# STM32F103-V1_0.net
KiCad netlist of a schematic drawn in Altium Designer
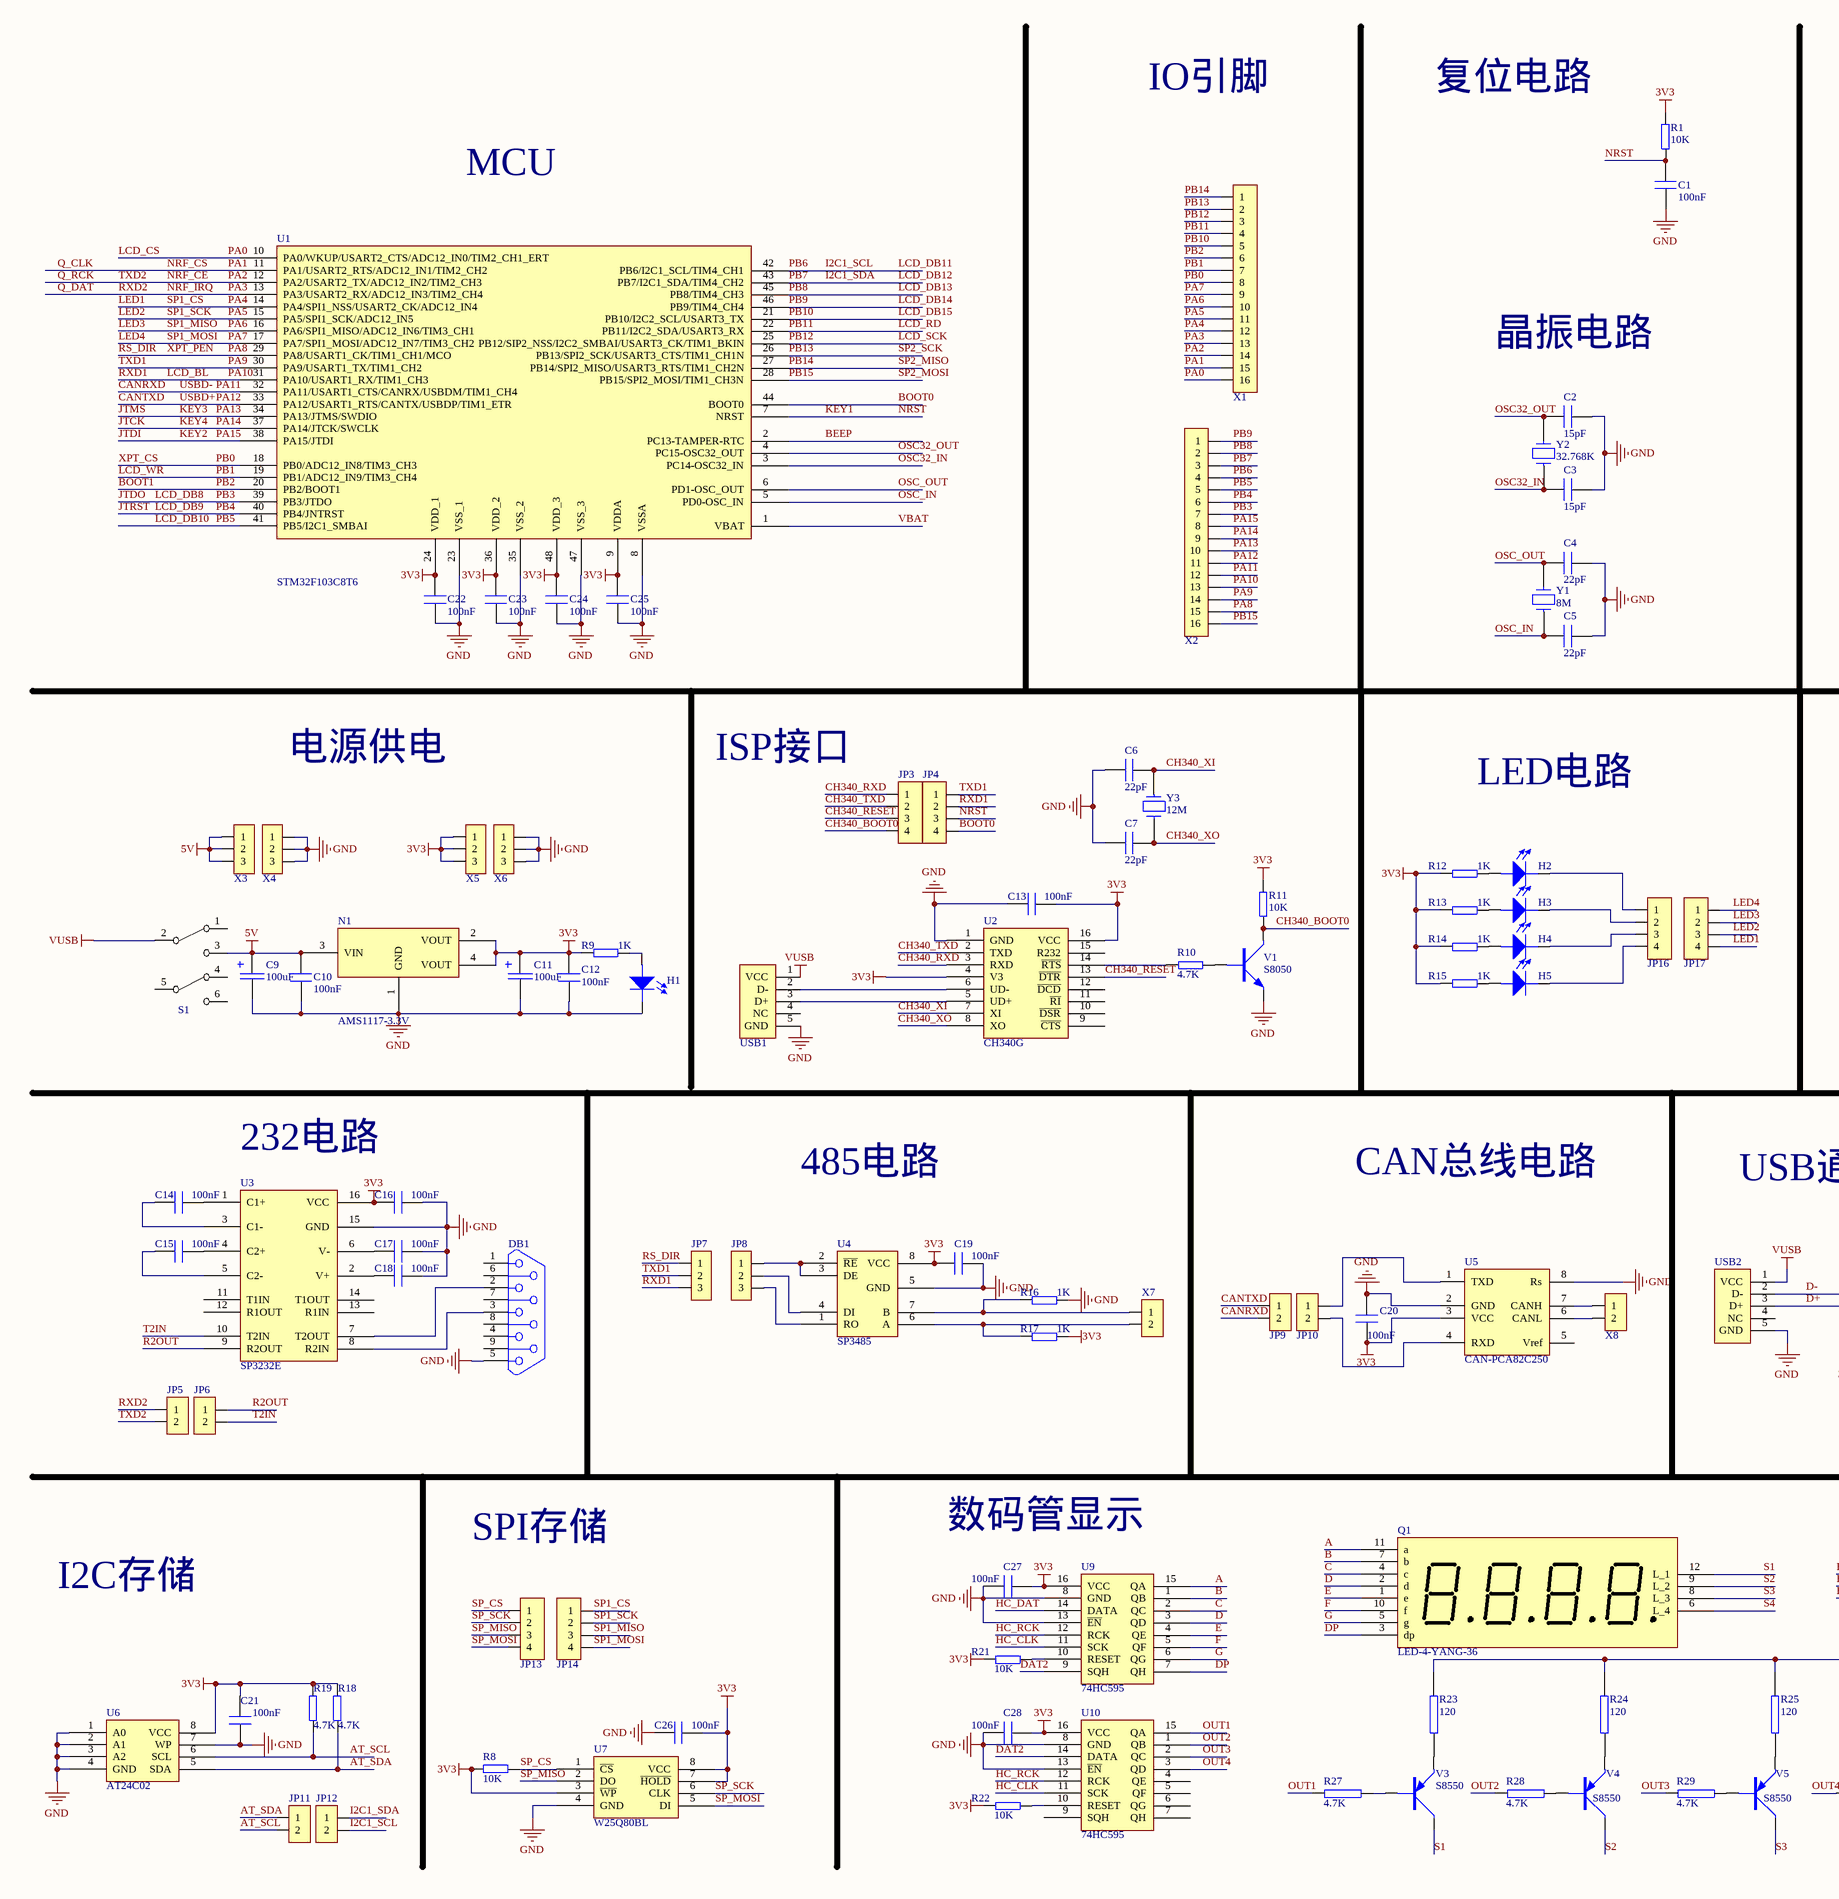
[diagram p0: STM32F103-V1.0.SchDoc, left]
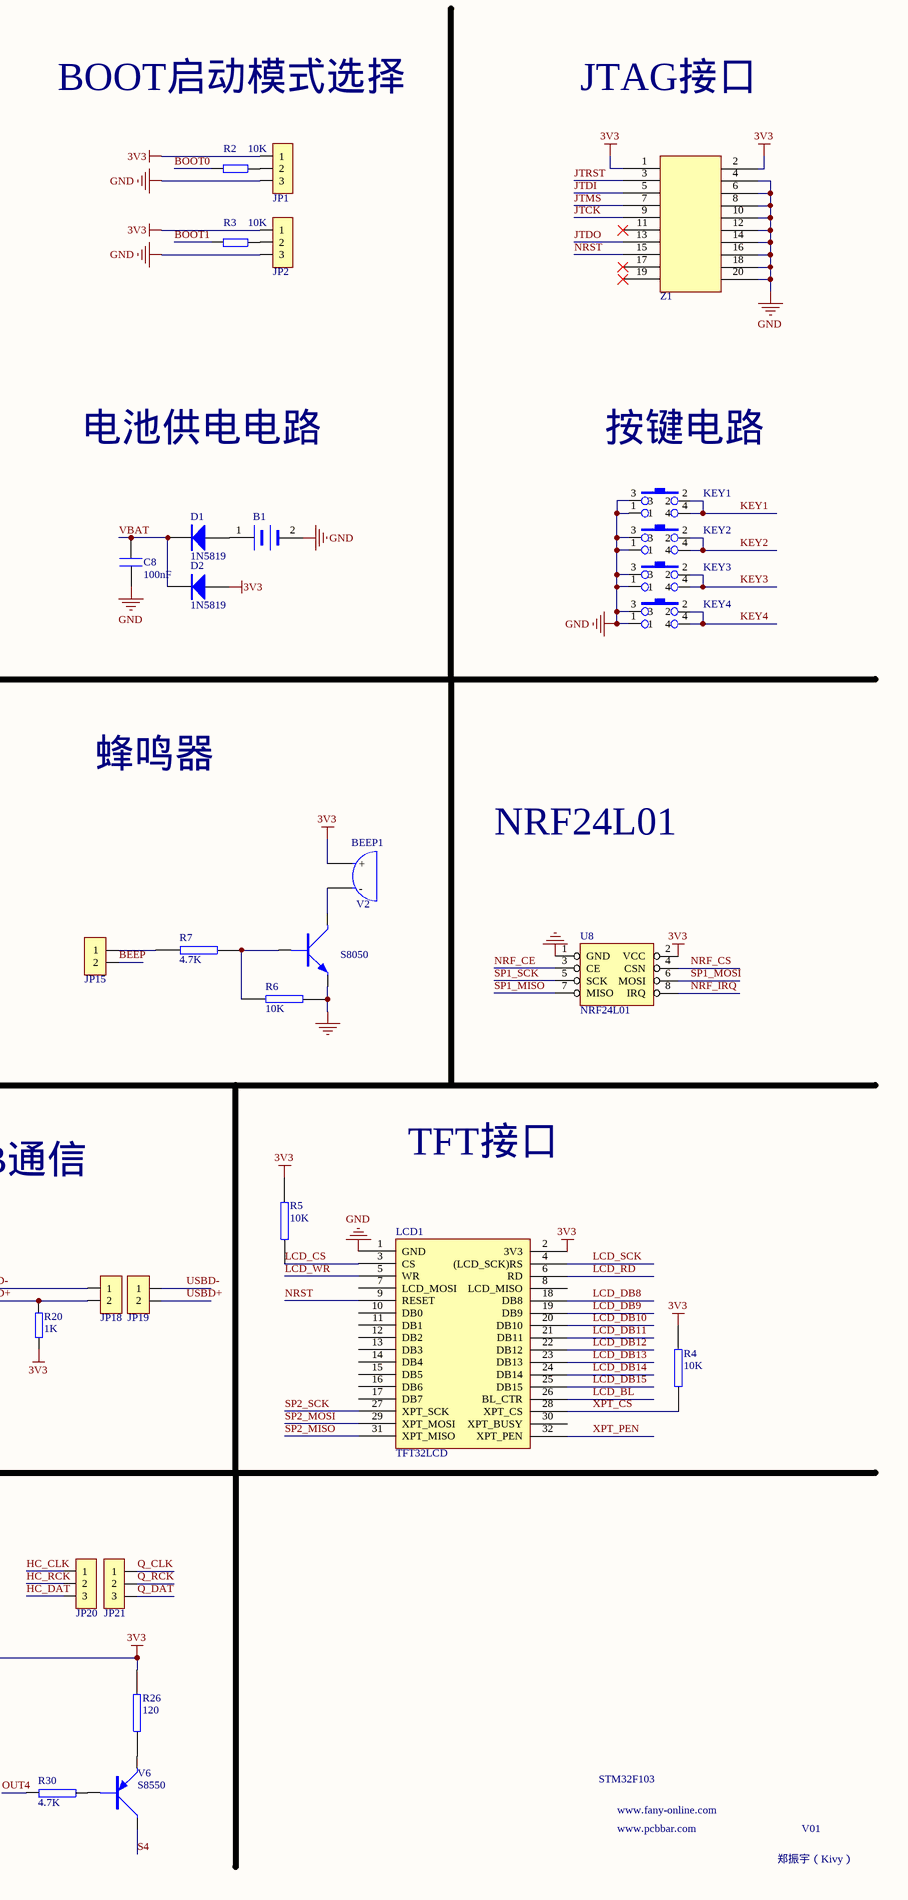
[diagram p1: STM32F103-V1.0.SchDoc, right]

(export (version "E")
  (design (tool "Eeschema 10.0.6"))
  (components
    (comp (ref "B1") (value "BATTERY") (footprint "CR1220") (libsource (lib "Liuzhx") (part "BATTERY")))
    (comp (ref "BEEP1") (value "BEEP") (footprint "SOT12-7.6") (libsource (lib "RationSTM32") (part "BEEP")))
    (comp (ref "C1")
      (value "100nF")
      (footprint "C0805")
      (description "Capacitor")
      (libsource (lib "Liuzhx") (part "普通贴片电容"))
    )
    (comp (ref "C2")
      (value "15pF")
      (footprint "C0805")
      (description "Capacitor")
      (libsource (lib "Liuzhx") (part "普通贴片电容"))
    )
    (comp (ref "C3")
      (value "15pF")
      (footprint "C0805")
      (description "Capacitor")
      (libsource (lib "Liuzhx") (part "普通贴片电容"))
    )
    (comp (ref "C4")
      (value "22pF")
      (footprint "C0805")
      (description "Capacitor")
      (libsource (lib "Liuzhx") (part "普通贴片电容"))
    )
    (comp (ref "C5")
      (value "22pF")
      (footprint "C0805")
      (description "Capacitor")
      (libsource (lib "Liuzhx") (part "普通贴片电容"))
    )
    (comp (ref "C6")
      (value "22pF")
      (footprint "C0805")
      (description "Capacitor")
      (libsource (lib "Liuzhx") (part "普通贴片电容"))
    )
    (comp (ref "C7")
      (value "22pF")
      (footprint "C0805")
      (description "Capacitor")
      (libsource (lib "Liuzhx") (part "普通贴片电容"))
    )
    (comp (ref "C8")
      (value "100nF")
      (footprint "C0805")
      (description "Capacitor")
      (libsource (lib "Liuzhx") (part "普通贴片电容"))
    )
    (comp (ref "C9") (value "100uF") (footprint "CAP5*5_4") (libsource (lib "Liuzhx") (part "极性电容器")))
    (comp (ref "C10")
      (value "100nF")
      (footprint "C0805")
      (description "Capacitor")
      (libsource (lib "Liuzhx") (part "普通贴片电容"))
    )
    (comp (ref "C11") (value "100uF") (footprint "CAP5*5_4") (libsource (lib "Liuzhx") (part "极性电容器")))
    (comp (ref "C12")
      (value "100nF")
      (footprint "C0805")
      (description "Capacitor")
      (libsource (lib "Liuzhx") (part "普通贴片电容"))
    )
    (comp (ref "C13")
      (value "100nF")
      (footprint "C0805")
      (description "Capacitor")
      (libsource (lib "Liuzhx") (part "普通贴片电容"))
    )
    (comp (ref "C14")
      (value "100nF")
      (footprint "C0805")
      (description "Capacitor")
      (libsource (lib "Liuzhx") (part "普通贴片电容"))
    )
    (comp (ref "C15")
      (value "100nF")
      (footprint "C0805")
      (description "Capacitor")
      (libsource (lib "Liuzhx") (part "普通贴片电容"))
    )
    (comp (ref "C16")
      (value "100nF")
      (footprint "C0805")
      (description "Capacitor")
      (libsource (lib "Liuzhx") (part "普通贴片电容"))
    )
    (comp (ref "C17")
      (value "100nF")
      (footprint "C0805")
      (description "Capacitor")
      (libsource (lib "Liuzhx") (part "普通贴片电容"))
    )
    (comp (ref "C18")
      (value "100nF")
      (footprint "C0805")
      (description "Capacitor")
      (libsource (lib "Liuzhx") (part "普通贴片电容"))
    )
    (comp (ref "C19")
      (value "100nF")
      (footprint "C0805")
      (description "Capacitor")
      (libsource (lib "Liuzhx") (part "普通贴片电容"))
    )
    (comp (ref "C20")
      (value "100nF")
      (footprint "C0805")
      (description "Capacitor")
      (libsource (lib "GKSSCH") (part "普通贴片电容"))
    )
    (comp (ref "C21")
      (value "100nF")
      (footprint "C0805")
      (description "Capacitor")
      (libsource (lib "Liuzhx") (part "普通贴片电容"))
    )
    (comp (ref "C22")
      (value "100nF")
      (footprint "C0805")
      (description "Capacitor")
      (libsource (lib "Liuzhx") (part "普通贴片电容"))
    )
    (comp (ref "C23")
      (value "100nF")
      (footprint "C0805")
      (description "Capacitor")
      (libsource (lib "Liuzhx") (part "普通贴片电容"))
    )
    (comp (ref "C24")
      (value "100nF")
      (footprint "C0805")
      (description "Capacitor")
      (libsource (lib "Liuzhx") (part "普通贴片电容"))
    )
    (comp (ref "C25")
      (value "100nF")
      (footprint "C0805")
      (description "Capacitor")
      (libsource (lib "Liuzhx") (part "普通贴片电容"))
    )
    (comp (ref "C26")
      (value "100nF")
      (footprint "C0805")
      (description "Capacitor")
      (libsource (lib "Liuzhx") (part "普通贴片电容"))
    )
    (comp (ref "C27")
      (value "100nF")
      (footprint "C0805")
      (description "Capacitor")
      (libsource (lib "Liuzhx") (part "普通贴片电容"))
    )
    (comp (ref "C28")
      (value "100nF")
      (footprint "C0805")
      (description "Capacitor")
      (libsource (lib "Liuzhx") (part "普通贴片电容"))
    )
    (comp (ref "D1")
      (value "1N5819")
      (footprint "1N4148-T")
      (description "Diode 1N series")
      (libsource (lib "Liuzhx") (part "贴片二极管"))
    )
    (comp (ref "D2")
      (value "1N5819")
      (footprint "1N4148-T")
      (description "Diode 1N series")
      (libsource (lib "Liuzhx") (part "贴片二极管"))
    )
    (comp (ref "DB1")
      (value "DB9M")
      (footprint "DB9-M")
      (description "母头")
      (libsource (lib "Liuzhx") (part "DB9M"))
    )
    (comp (ref "H1") (value "发光二极管") (footprint "LED1206") (libsource (lib "Liuzhx") (part "发光二极管")))
    (comp (ref "H2") (value "发光二极管") (footprint "LED1206") (libsource (lib "Liuzhx") (part "发光二极管")))
    (comp (ref "H3") (value "发光二极管") (footprint "LED1206") (libsource (lib "Liuzhx") (part "发光二极管")))
    (comp (ref "H4") (value "发光二极管") (footprint "LED1206") (libsource (lib "Liuzhx") (part "发光二极管")))
    (comp (ref "H5") (value "发光二极管") (footprint "LED1206") (libsource (lib "Liuzhx") (part "发光二极管")))
    (comp (ref "JP1")
      (value "JX3")
      (footprint "SIP3")
      (description "Connector")
      (libsource (lib "Liuzhx") (part "JX3"))
    )
    (comp (ref "JP2")
      (value "JX3")
      (footprint "SIP3")
      (description "Connector")
      (libsource (lib "Liuzhx") (part "JX3"))
    )
    (comp (ref "JP3")
      (value "JX4")
      (footprint "SIP4")
      (description "Connector")
      (libsource (lib "Liuzhx") (part "JX4"))
    )
    (comp (ref "JP4")
      (value "JX4")
      (footprint "SIP4")
      (description "Connector")
      (libsource (lib "") (part "JX4_1"))
    )
    (comp (ref "JP5")
      (value "JX2")
      (footprint "SIP2")
      (description "Connector")
      (libsource (lib "") (part "JX2_1"))
    )
    (comp (ref "JP6")
      (value "JX2")
      (footprint "SIP2")
      (description "Connector")
      (libsource (lib "Liuzhx") (part "JX2"))
    )
    (comp (ref "JP7")
      (value "JX3")
      (footprint "SIP3")
      (description "Connector")
      (libsource (lib "Liuzhx") (part "JX3"))
    )
    (comp (ref "JP8")
      (value "JX3")
      (footprint "SIP3")
      (description "Connector")
      (libsource (lib "") (part "JX3_1"))
    )
    (comp (ref "JP9")
      (value "JX2")
      (footprint "SIP2")
      (description "Connector")
      (libsource (lib "GKSSCH") (part "JX2"))
    )
    (comp (ref "JP10")
      (value "JX2")
      (footprint "SIP2")
      (description "Connector")
      (libsource (lib "") (part "JX2_1"))
    )
    (comp (ref "JP11")
      (value "JX2")
      (footprint "SIP2")
      (description "Connector")
      (libsource (lib "") (part "JX2_1"))
    )
    (comp (ref "JP12")
      (value "JX2")
      (footprint "SIP2")
      (description "Connector")
      (libsource (lib "Liuzhx") (part "JX2"))
    )
    (comp (ref "JP13")
      (value "JX4")
      (footprint "SIP4")
      (description "Connector")
      (libsource (lib "Liuzhx") (part "JX4"))
    )
    (comp (ref "JP14")
      (value "JX4")
      (footprint "SIP4")
      (description "Connector")
      (libsource (lib "") (part "JX4_1"))
    )
    (comp (ref "JP15")
      (value "JX2")
      (footprint "SIP2")
      (description "Connector")
      (libsource (lib "Liuzhx") (part "JX2"))
    )
    (comp (ref "JP16")
      (value "JX4")
      (footprint "SIP4")
      (description "Connector")
      (libsource (lib "Liuzhx") (part "JX4"))
    )
    (comp (ref "JP17")
      (value "JX4")
      (footprint "SIP4")
      (description "Connector")
      (libsource (lib "") (part "JX4_1"))
    )
    (comp (ref "JP18")
      (value "JX2")
      (footprint "SIP2")
      (description "Connector")
      (libsource (lib "") (part "JX2_1"))
    )
    (comp (ref "JP19")
      (value "JX2")
      (footprint "SIP2")
      (description "Connector")
      (libsource (lib "Liuzhx") (part "JX2"))
    )
    (comp (ref "JP20")
      (value "JX3")
      (footprint "SIP3")
      (description "Connector")
      (libsource (lib "Liuzhx") (part "JX3"))
    )
    (comp (ref "JP21")
      (value "JX3")
      (footprint "SIP3")
      (description "Connector")
      (libsource (lib "") (part "JX3_1"))
    )
    (comp (ref "KEY1") (value "SW-66B7") (footprint "SW-66") (libsource (lib "Liuzhx") (part "SW-66B7")))
    (comp (ref "KEY2") (value "SW-66B7") (footprint "SW-66") (libsource (lib "Liuzhx") (part "SW-66B7")))
    (comp (ref "KEY3") (value "SW-66B7") (footprint "SW-66") (libsource (lib "Liuzhx") (part "SW-66B7")))
    (comp (ref "KEY4") (value "SW-66B7") (footprint "SW-66") (libsource (lib "Liuzhx") (part "SW-66B7")))
    (comp (ref "LCD1") (value "TFT32LCD") (footprint "HEAD16×2") (libsource (lib "Liuzhx") (part "TFT32LCD")))
    (comp (ref "N1")
      (value "AMS1117-3.3V")
      (footprint "SOT223")
      (libsource (lib "Liuzhx") (part "AMS1117-3.3V"))
    )
    (comp (ref "Q1")
      (value "LED-4-YANG-36")
      (footprint "LED0.36-4")
      (libsource (lib "Liuzhx") (part "LED-4-YANG-36"))
    )
    (comp (ref "R1") (value "10K") (footprint "R0805") (libsource (lib "Liuzhx") (part "普通贴片电阻")))
    (comp (ref "R2") (value "10K") (footprint "R0805") (libsource (lib "Liuzhx") (part "普通贴片电阻")))
    (comp (ref "R3") (value "10K") (footprint "R0805") (libsource (lib "Liuzhx") (part "普通贴片电阻")))
    (comp (ref "R4") (value "10K") (footprint "R0805") (libsource (lib "RationSTM32") (part "RES")))
    (comp (ref "R5") (value "10K") (footprint "R0805") (libsource (lib "RationSTM32") (part "RES")))
    (comp (ref "R6") (value "10K") (footprint "R0805") (libsource (lib "RationSTM32") (part "RES")))
    (comp (ref "R7") (value "4.7K") (footprint "R0805") (libsource (lib "RationSTM32") (part "RES")))
    (comp (ref "R8") (value "10K") (footprint "R0805") (libsource (lib "Liuzhx") (part "普通贴片电阻")))
    (comp (ref "R9") (value "1K") (footprint "R0805") (libsource (lib "Liuzhx") (part "普通贴片电阻")))
    (comp (ref "R10") (value "4.7K") (footprint "R0805") (libsource (lib "Liuzhx") (part "普通贴片电阻")))
    (comp (ref "R11") (value "10K") (footprint "R0805") (libsource (lib "Liuzhx") (part "普通贴片电阻")))
    (comp (ref "R12") (value "1K") (footprint "R0805") (libsource (lib "Liuzhx") (part "普通贴片电阻")))
    (comp (ref "R13") (value "1K") (footprint "R0805") (libsource (lib "Liuzhx") (part "普通贴片电阻")))
    (comp (ref "R14") (value "1K") (footprint "R0805") (libsource (lib "Liuzhx") (part "普通贴片电阻")))
    (comp (ref "R15") (value "1K") (footprint "R0805") (libsource (lib "Liuzhx") (part "普通贴片电阻")))
    (comp (ref "R16") (value "1K") (footprint "R0805") (libsource (lib "Liuzhx") (part "普通贴片电阻")))
    (comp (ref "R17") (value "1K") (footprint "R0805") (libsource (lib "Liuzhx") (part "普通贴片电阻")))
    (comp (ref "R18") (value "4.7K") (footprint "R0805") (libsource (lib "Liuzhx") (part "普通贴片电阻")))
    (comp (ref "R19") (value "4.7K") (footprint "R0805") (libsource (lib "Liuzhx") (part "普通贴片电阻")))
    (comp (ref "R20") (value "1K") (footprint "R0805") (libsource (lib "Liuzhx") (part "普通贴片电阻")))
    (comp (ref "R21") (value "10K") (footprint "R0805") (libsource (lib "Liuzhx") (part "普通贴片电阻")))
    (comp (ref "R22") (value "10K") (footprint "R0805") (libsource (lib "Liuzhx") (part "普通贴片电阻")))
    (comp (ref "R23") (value "120") (footprint "R0805") (libsource (lib "STM32F103-V1.0") (part "RES")))
    (comp (ref "R24") (value "120") (footprint "R0805") (libsource (lib "STM32F103-V1.0") (part "RES")))
    (comp (ref "R25") (value "120") (footprint "R0805") (libsource (lib "STM32F103-V1.0") (part "RES")))
    (comp (ref "R26") (value "120") (footprint "R0805") (libsource (lib "STM32F103-V1.0") (part "RES")))
    (comp (ref "R27") (value "4.7K") (footprint "R0805") (libsource (lib "STM32F103-V1.0") (part "RES2")))
    (comp (ref "R28") (value "4.7K") (footprint "R0805") (libsource (lib "STM32F103-V1.0") (part "RES2")))
    (comp (ref "R29") (value "4.7K") (footprint "R0805") (libsource (lib "STM32F103-V1.0") (part "RES2")))
    (comp (ref "R30") (value "4.7K") (footprint "R0805") (libsource (lib "STM32F103-V1.0") (part "RES2")))
    (comp (ref "S1") (value "SWITCH-6") (footprint "SW-AJ") (libsource (lib "Liuzhx") (part "SWITCH-6")))
    (comp (ref "U1")
      (value "STM32F103C8T6")
      (footprint "LQFP48")
      (libsource (lib "STM32F103-V1.0") (part "STM32F103C8T6"))
    )
    (comp (ref "U2") (value "CH340G") (footprint "SOIC16") (libsource (lib "Liuzhx") (part "CH340G")))
    (comp (ref "U3")
      (value "SP3232E")
      (footprint "SOIC16")
      (description "SP3232EEN-L/TR;SOIC-39MM")
      (libsource (lib "Liuzhx") (part "SP3232E"))
    )
    (comp (ref "U4") (value "SP3485") (footprint "SO-8") (libsource (lib "Liuzhx") (part "MAX3082")))
    (comp (ref "U5")
      (value "CAN-PCA82C250")
      (footprint "SO-8")
      (libsource (lib "GKSSCH") (part "CAN-PCA82C250"))
    )
    (comp (ref "U6") (value "AT24C02") (footprint "SO-8") (libsource (lib "Liuzhx") (part "AT24C02")))
    (comp (ref "U7") (value "W25Q80BL") (footprint "W25Q-SO8") (libsource (lib "Liuzhx") (part "W25Q80BL")))
    (comp (ref "U8") (value "NRF24L01") (footprint "NRF24L01") (libsource (lib "Liuzhx") (part "NRF24L01")))
    (comp (ref "U9")
      (value "74HC595")
      (footprint "SO-16")
      (description "串入并出移位寄存器")
      (libsource (lib "Liuzhx") (part "74HC595"))
    )
    (comp (ref "U10")
      (value "74HC595")
      (footprint "SO-16")
      (description "串入并出移位寄存器")
      (libsource (lib "Liuzhx") (part "74HC595"))
    )
    (comp (ref "USB1")
      (value "MicroUSB")
      (footprint "MicroUSB1")
      (description "母头")
      (libsource (lib "Liuzhx") (part "MicroUSB"))
    )
    (comp (ref "USB2")
      (value "MicroUSB")
      (footprint "MicroUSB1")
      (description "母头")
      (libsource (lib "Liuzhx") (part "MicroUSB"))
    )
    (comp (ref "V1")
      (value "S8050")
      (footprint "SOT23-C1")
      (description "V")
      (libsource (lib "Liuzhx") (part "NPN三极管"))
    )
    (comp (ref "V2")
      (value "S8050")
      (footprint "SOT23-C1")
      (description "V")
      (libsource (lib "Liuzhx") (part "NPN三极管"))
    )
    (comp (ref "V3")
      (value "S8550")
      (footprint "SOT23-C1")
      (description "V")
      (libsource (lib "*") (part "PNP三极管"))
    )
    (comp (ref "V4")
      (value "S8550")
      (footprint "SOT23-C1")
      (description "V")
      (libsource (lib "*") (part "PNP三极管"))
    )
    (comp (ref "V5")
      (value "S8550")
      (footprint "SOT23-C1")
      (description "V")
      (libsource (lib "*") (part "PNP三极管"))
    )
    (comp (ref "V6")
      (value "S8550")
      (footprint "SOT23-C1")
      (description "V")
      (libsource (lib "*") (part "PNP三极管"))
    )
    (comp (ref "X1") (value "JX16") (footprint "SIP16") (libsource (lib "") (part "JX16_1")))
    (comp (ref "X2") (value "JX16") (footprint "SIP16") (libsource (lib "Liuzhx") (part "JX16")))
    (comp (ref "X3")
      (value "JX3")
      (footprint "SIP3")
      (description "Connector")
      (libsource (lib "Liuzhx") (part "JX3"))
    )
    (comp (ref "X4")
      (value "JX3")
      (footprint "SIP3")
      (description "Connector")
      (libsource (lib "") (part "JX3_1"))
    )
    (comp (ref "X5")
      (value "JX3")
      (footprint "SIP3")
      (description "Connector")
      (libsource (lib "Liuzhx") (part "JX3"))
    )
    (comp (ref "X6")
      (value "JX3")
      (footprint "SIP3")
      (description "Connector")
      (libsource (lib "") (part "JX3_1"))
    )
    (comp (ref "X7")
      (value "JX2")
      (footprint "WJ128-5.0-2P")
      (description "Connector")
      (libsource (lib "") (part "JX2_1"))
    )
    (comp (ref "X8")
      (value "JX2")
      (footprint "WJ128-5.0-2P")
      (description "Connector")
      (libsource (lib "GKSSCH") (part "JX2"))
    )
    (comp (ref "Y1")
      (value "8M")
      (footprint "JZ-AX")
      (description "Crystal")
      (libsource (lib "Liuzhx") (part "CRYSTAL"))
    )
    (comp (ref "Y2")
      (value "32.768K")
      (footprint "FC135")
      (description "Crystal")
      (libsource (lib "Liuzhx") (part "CRYSTAL"))
    )
    (comp (ref "Y3")
      (value "12M")
      (footprint "JZ-AX")
      (description "Crystal")
      (libsource (lib "Liuzhx") (part "CRYSTAL"))
    )
    (comp (ref "Z1") (value "HEADER 10X2") (footprint "JTAG") (libsource (lib "STM32") (part "HEADER 10X2")))
  )
  (nets
    (net (code "1") (name "/A") (class "Default")
      (node (ref "Q1") (pin "11") (pinfunction "a_11") (pintype "passive"))
      (node (ref "U9") (pin "15") (pinfunction "QA_15") (pintype "passive"))
    )
    (net (code "2") (name "/AT_SCL") (class "Default")
      (node (ref "JP11") (pin "2") (pinfunction "2_2") (pintype "passive"))
      (node (ref "R19") (pin "1") (pinfunction "1_1") (pintype "passive"))
      (node (ref "U6") (pin "6") (pinfunction "SCL_6") (pintype "passive"))
    )
    (net (code "3") (name "/AT_SDA") (class "Default")
      (node (ref "JP11") (pin "1") (pinfunction "1_1") (pintype "passive"))
      (node (ref "R18") (pin "1") (pinfunction "1_1") (pintype "passive"))
      (node (ref "U6") (pin "5") (pinfunction "SDA_5") (pintype "passive"))
    )
    (net (code "4") (name "/B") (class "Default")
      (node (ref "Q1") (pin "7") (pinfunction "b_7") (pintype "passive"))
      (node (ref "U9") (pin "1") (pinfunction "QB_1") (pintype "passive"))
    )
    (net (code "5") (name "/BEEP") (class "Default")
      (node (ref "JP15") (pin "2") (pinfunction "2_2") (pintype "passive"))
      (node (ref "U1") (pin "2") (pinfunction "PC13-TAMPER-RTC_2") (pintype "passive"))
    )
    (net (code "6") (name "/BOOT0") (class "Default")
      (node (ref "JP4") (pin "4") (pinfunction "4_4") (pintype "passive"))
      (node (ref "R2") (pin "1") (pinfunction "1_1") (pintype "passive"))
      (node (ref "U1") (pin "44") (pinfunction "BOOT0_44") (pintype "passive"))
    )
    (net (code "7") (name "/BOOT1") (class "Default")
      (node (ref "R3") (pin "1") (pinfunction "1_1") (pintype "passive"))
      (node (ref "U1") (pin "20") (pinfunction "PB2/BOOT1_20") (pintype "passive"))
      (node (ref "X1") (pin "6") (pinfunction "6_6") (pintype "passive"))
    )
    (net (code "8") (name "/C") (class "Default")
      (node (ref "Q1") (pin "4") (pinfunction "c_4") (pintype "passive"))
      (node (ref "U9") (pin "2") (pinfunction "QC_2") (pintype "passive"))
    )
    (net (code "9") (name "/CANRXD") (class "Default")
      (node (ref "JP19") (pin "1") (pinfunction "1_1") (pintype "passive"))
      (node (ref "JP9") (pin "2") (pinfunction "2_2") (pintype "passive"))
      (node (ref "U1") (pin "32") (pinfunction "PA11/USART1_CTS/CANRX/USBDM/TIM1_CH4_32") (pintype "passive"))
      (node (ref "X2") (pin "12") (pinfunction "12_12") (pintype "passive"))
    )
    (net (code "10") (name "/CANTXD") (class "Default")
      (node (ref "JP19") (pin "2") (pinfunction "2_2") (pintype "passive"))
      (node (ref "JP9") (pin "1") (pinfunction "1_1") (pintype "passive"))
      (node (ref "U1") (pin "33") (pinfunction "PA12/USART1_RTS/CANTX/USBDP/TIM1_ETR_33") (pintype "passive"))
      (node (ref "X2") (pin "11") (pinfunction "11_11") (pintype "passive"))
    )
    (net (code "11") (name "/CH340_BOOT0") (class "Default")
      (node (ref "JP3") (pin "4") (pinfunction "4_4") (pintype "passive"))
      (node (ref "R11") (pin "1") (pinfunction "1_1") (pintype "passive"))
      (node (ref "V1") (pin "C") (pinfunction "C_C") (pintype "passive"))
    )
    (net (code "12") (name "/CH340_RESET") (class "Default")
      (node (ref "JP3") (pin "3") (pinfunction "3_3") (pintype "passive"))
      (node (ref "U2") (pin "13") (pinfunction "~{DTR}_13") (pintype "passive"))
    )
    (net (code "13") (name "/CH340_RXD") (class "Default")
      (node (ref "JP3") (pin "1") (pinfunction "1_1") (pintype "passive"))
      (node (ref "U2") (pin "3") (pinfunction "RXD_3") (pintype "passive"))
    )
    (net (code "14") (name "/CH340_TXD") (class "Default")
      (node (ref "JP3") (pin "2") (pinfunction "2_2") (pintype "passive"))
      (node (ref "U2") (pin "2") (pinfunction "TXD_2") (pintype "passive"))
    )
    (net (code "15") (name "/CH340_XI") (class "Default")
      (node (ref "C6") (pin "2") (pinfunction "2_2") (pintype "passive"))
      (node (ref "U2") (pin "7") (pinfunction "XI_7") (pintype "passive"))
      (node (ref "Y3") (pin "1") (pinfunction "1_1") (pintype "passive"))
    )
    (net (code "16") (name "/CH340_XO") (class "Default")
      (node (ref "C7") (pin "2") (pinfunction "2_2") (pintype "passive"))
      (node (ref "U2") (pin "8") (pinfunction "XO_8") (pintype "passive"))
      (node (ref "Y3") (pin "2") (pinfunction "2_2") (pintype "passive"))
    )
    (net (code "17") (name "/D") (class "Default")
      (node (ref "Q1") (pin "2") (pinfunction "d_2") (pintype "passive"))
      (node (ref "U9") (pin "3") (pinfunction "QD_3") (pintype "passive"))
    )
    (net (code "18") (name "/D+") (class "Default")
      (node (ref "JP18") (pin "2") (pinfunction "2_2") (pintype "passive"))
      (node (ref "R20") (pin "1") (pinfunction "1_1") (pintype "passive"))
      (node (ref "USB2") (pin "3") (pinfunction "D+_3") (pintype "passive"))
    )
    (net (code "19") (name "/D-") (class "Default")
      (node (ref "JP18") (pin "1") (pinfunction "1_1") (pintype "passive"))
      (node (ref "USB2") (pin "2") (pinfunction "D-_2") (pintype "passive"))
    )
    (net (code "20") (name "/DAT2") (class "Default")
      (node (ref "U10") (pin "14") (pinfunction "DATA_14") (pintype "passive"))
      (node (ref "U9") (pin "9") (pinfunction "SQH_9") (pintype "passive"))
    )
    (net (code "21") (name "/DP") (class "Default")
      (node (ref "Q1") (pin "3") (pinfunction "dp_3") (pintype "passive"))
      (node (ref "U9") (pin "7") (pinfunction "QH_7") (pintype "passive"))
    )
    (net (code "22") (name "/E") (class "Default")
      (node (ref "Q1") (pin "1") (pinfunction "e_1") (pintype "passive"))
      (node (ref "U9") (pin "4") (pinfunction "QE_4") (pintype "passive"))
    )
    (net (code "23") (name "/F") (class "Default")
      (node (ref "Q1") (pin "10") (pinfunction "f_10") (pintype "passive"))
      (node (ref "U9") (pin "5") (pinfunction "QF_5") (pintype "passive"))
    )
    (net (code "24") (name "/G") (class "Default")
      (node (ref "Q1") (pin "5") (pinfunction "g_5") (pintype "passive"))
      (node (ref "U9") (pin "6") (pinfunction "QG_6") (pintype "passive"))
    )
    (net (code "25") (name "/HC_CLK") (class "Default")
      (node (ref "JP20") (pin "1") (pinfunction "1_1") (pintype "passive"))
      (node (ref "U10") (pin "11") (pinfunction "SCK_11") (pintype "passive"))
      (node (ref "U9") (pin "11") (pinfunction "SCK_11") (pintype "passive"))
    )
    (net (code "26") (name "/HC_DAT") (class "Default")
      (node (ref "JP20") (pin "3") (pinfunction "3_3") (pintype "passive"))
      (node (ref "U9") (pin "14") (pinfunction "DATA_14") (pintype "passive"))
    )
    (net (code "27") (name "/HC_RCK") (class "Default")
      (node (ref "JP20") (pin "2") (pinfunction "2_2") (pintype "passive"))
      (node (ref "U10") (pin "12") (pinfunction "RCK_12") (pintype "passive"))
      (node (ref "U9") (pin "12") (pinfunction "RCK_12") (pintype "passive"))
    )
    (net (code "28") (name "/I2C1_SCL") (class "Default")
      (node (ref "JP12") (pin "2") (pinfunction "2_2") (pintype "passive"))
      (node (ref "LCD1") (pin "21") (pinfunction "DB11_21") (pintype "passive"))
      (node (ref "U1") (pin "42") (pinfunction "PB6/I2C1_SCL/TIM4_CH1_42") (pintype "passive"))
      (node (ref "X2") (pin "4") (pinfunction "4_4") (pintype "passive"))
    )
    (net (code "29") (name "/I2C1_SDA") (class "Default")
      (node (ref "JP12") (pin "1") (pinfunction "1_1") (pintype "passive"))
      (node (ref "LCD1") (pin "22") (pinfunction "DB12_22") (pintype "passive"))
      (node (ref "U1") (pin "43") (pinfunction "PB7/I2C1_SDA/TIM4_CH2_43") (pintype "passive"))
      (node (ref "X2") (pin "3") (pinfunction "3_3") (pintype "passive"))
    )
    (net (code "30") (name "/JTCK") (class "Default")
      (node (ref "KEY4") (pin "2") (pinfunction "2_2") (pintype "passive"))
      (node (ref "KEY4") (pin "4") (pinfunction "4_4") (pintype "passive"))
      (node (ref "U1") (pin "37") (pinfunction "PA14/JTCK/SWCLK_37") (pintype "passive"))
      (node (ref "X2") (pin "9") (pinfunction "9_9") (pintype "passive"))
      (node (ref "Z1") (pin "9") (pinfunction "9_9") (pintype "passive"))
    )
    (net (code "31") (name "/JTDI") (class "Default")
      (node (ref "KEY2") (pin "2") (pinfunction "2_2") (pintype "passive"))
      (node (ref "KEY2") (pin "4") (pinfunction "4_4") (pintype "passive"))
      (node (ref "U1") (pin "38") (pinfunction "PA15/JTDI_38") (pintype "passive"))
      (node (ref "X2") (pin "8") (pinfunction "8_8") (pintype "passive"))
      (node (ref "Z1") (pin "5") (pinfunction "5_5") (pintype "passive"))
    )
    (net (code "32") (name "/JTDO") (class "Default")
      (node (ref "LCD1") (pin "18") (pinfunction "DB8_18") (pintype "passive"))
      (node (ref "U1") (pin "39") (pinfunction "PB3/JTDO_39") (pintype "passive"))
      (node (ref "X2") (pin "7") (pinfunction "7_7") (pintype "passive"))
      (node (ref "Z1") (pin "13") (pinfunction "13_13") (pintype "passive"))
    )
    (net (code "33") (name "/JTMS") (class "Default")
      (node (ref "KEY3") (pin "2") (pinfunction "2_2") (pintype "passive"))
      (node (ref "KEY3") (pin "4") (pinfunction "4_4") (pintype "passive"))
      (node (ref "U1") (pin "34") (pinfunction "PA13/JTMS/SWDIO_34") (pintype "passive"))
      (node (ref "X2") (pin "10") (pinfunction "10_10") (pintype "passive"))
      (node (ref "Z1") (pin "7") (pinfunction "7_7") (pintype "passive"))
    )
    (net (code "34") (name "/JTRST") (class "Default")
      (node (ref "LCD1") (pin "19") (pinfunction "DB9_19") (pintype "passive"))
      (node (ref "U1") (pin "40") (pinfunction "PB4/JNTRST_40") (pintype "passive"))
      (node (ref "X2") (pin "6") (pinfunction "6_6") (pintype "passive"))
      (node (ref "Z1") (pin "3") (pinfunction "3_3") (pintype "passive"))
    )
    (net (code "35") (name "/KEY1") (class "Default")
      (node (ref "C1") (pin "2") (pinfunction "2_2") (pintype "passive"))
      (node (ref "JP4") (pin "3") (pinfunction "3_3") (pintype "passive"))
      (node (ref "KEY1") (pin "2") (pinfunction "2_2") (pintype "passive"))
      (node (ref "KEY1") (pin "4") (pinfunction "4_4") (pintype "passive"))
      (node (ref "LCD1") (pin "9") (pinfunction "RESET_9") (pintype "passive"))
      (node (ref "R1") (pin "1") (pinfunction "1_1") (pintype "passive"))
      (node (ref "U1") (pin "7") (pinfunction "NRST_7") (pintype "passive"))
      (node (ref "Z1") (pin "15") (pinfunction "15_15") (pintype "passive"))
    )
    (net (code "36") (name "/LCD_BL") (class "Default")
      (node (ref "JP4") (pin "2") (pinfunction "2_2") (pintype "passive"))
      (node (ref "JP7") (pin "3") (pinfunction "3_3") (pintype "passive"))
      (node (ref "LCD1") (pin "26") (pinfunction "BL_CTR_26") (pintype "passive"))
      (node (ref "U1") (pin "31") (pinfunction "PA10/USART1_RX/TIM1_CH3_31") (pintype "passive"))
      (node (ref "X2") (pin "13") (pinfunction "13_13") (pintype "passive"))
    )
    (net (code "37") (name "/LCD_CS") (class "Default")
      (node (ref "LCD1") (pin "3") (pinfunction "CS_3") (pintype "passive"))
      (node (ref "R5") (pin "1") (pinfunction "1_1") (pintype "passive"))
      (node (ref "U1") (pin "10") (pinfunction "PA0/WKUP/USART2_CTS/ADC12_IN0/TIM2_CH1_ERT_10") (pintype "passive"))
      (node (ref "X1") (pin "16") (pinfunction "16_16") (pintype "passive"))
    )
    (net (code "38") (name "/LCD_DB10") (class "Default")
      (node (ref "LCD1") (pin "20") (pinfunction "DB10_20") (pintype "passive"))
      (node (ref "U1") (pin "41") (pinfunction "PB5/I2C1_SMBAI_41") (pintype "passive"))
      (node (ref "X2") (pin "5") (pinfunction "5_5") (pintype "passive"))
    )
    (net (code "39") (name "/LCD_DB13") (class "Default")
      (node (ref "LCD1") (pin "23") (pinfunction "DB13_23") (pintype "passive"))
      (node (ref "U1") (pin "45") (pinfunction "PB8/TIM4_CH3_45") (pintype "passive"))
      (node (ref "X2") (pin "2") (pinfunction "2_2") (pintype "passive"))
    )
    (net (code "40") (name "/LCD_DB14") (class "Default")
      (node (ref "LCD1") (pin "24") (pinfunction "DB14_24") (pintype "passive"))
      (node (ref "U1") (pin "46") (pinfunction "PB9/TIM4_CH4_46") (pintype "passive"))
      (node (ref "X2") (pin "1") (pinfunction "1_1") (pintype "passive"))
    )
    (net (code "41") (name "/LCD_DB15") (class "Default")
      (node (ref "LCD1") (pin "25") (pinfunction "DB15_25") (pintype "passive"))
      (node (ref "U1") (pin "21") (pinfunction "PB10/I2C2_SCL/USART3_TX_21") (pintype "passive"))
      (node (ref "X1") (pin "5") (pinfunction "5_5") (pintype "passive"))
    )
    (net (code "42") (name "/LCD_RD") (class "Default")
      (node (ref "LCD1") (pin "6") (pinfunction "RD_6") (pintype "passive"))
      (node (ref "U1") (pin "22") (pinfunction "PB11/I2C2_SDA/USART3_RX_22") (pintype "passive"))
      (node (ref "X1") (pin "4") (pinfunction "4_4") (pintype "passive"))
    )
    (net (code "43") (name "/LCD_SCK") (class "Default")
      (node (ref "LCD1") (pin "4") (pinfunction "(LCD_SCK)RS_4") (pintype "passive"))
      (node (ref "U1") (pin "25") (pinfunction "PB12/SIP2_NSS/I2C2_SMBAI/USART3_CK/TIM1_BKIN_25") (pintype "passive"))
      (node (ref "X1") (pin "3") (pinfunction "3_3") (pintype "passive"))
    )
    (net (code "44") (name "/LCD_WR") (class "Default")
      (node (ref "LCD1") (pin "5") (pinfunction "WR_5") (pintype "passive"))
      (node (ref "U1") (pin "19") (pinfunction "PB1/ADC12_IN9/TIM3_CH4_19") (pintype "passive"))
      (node (ref "X1") (pin "7") (pinfunction "7_7") (pintype "passive"))
    )
    (net (code "45") (name "/LED1") (class "Default")
      (node (ref "JP14") (pin "1") (pinfunction "1_1") (pintype "passive"))
      (node (ref "JP17") (pin "4") (pinfunction "4_4") (pintype "passive"))
      (node (ref "U1") (pin "14") (pinfunction "PA4/SPI1_NSS/USART2_CK/ADC12_IN4_14") (pintype "passive"))
      (node (ref "X1") (pin "12") (pinfunction "12_12") (pintype "passive"))
    )
    (net (code "46") (name "/LED2") (class "Default")
      (node (ref "JP14") (pin "2") (pinfunction "2_2") (pintype "passive"))
      (node (ref "JP17") (pin "3") (pinfunction "3_3") (pintype "passive"))
      (node (ref "U1") (pin "15") (pinfunction "PA5/SPI1_SCK/ADC12_IN5_15") (pintype "passive"))
      (node (ref "U8") (pin "5") (pinfunction "SCK_5") (pintype "passive"))
      (node (ref "X1") (pin "11") (pinfunction "11_11") (pintype "passive"))
    )
    (net (code "47") (name "/LED3") (class "Default")
      (node (ref "JP14") (pin "3") (pinfunction "3_3") (pintype "passive"))
      (node (ref "JP17") (pin "2") (pinfunction "2_2") (pintype "passive"))
      (node (ref "U1") (pin "16") (pinfunction "PA6/SPI1_MISO/ADC12_IN6/TIM3_CH1_16") (pintype "passive"))
      (node (ref "U8") (pin "7") (pinfunction "MISO_7") (pintype "passive"))
      (node (ref "X1") (pin "10") (pinfunction "10_10") (pintype "passive"))
    )
    (net (code "48") (name "/LED4") (class "Default")
      (node (ref "JP14") (pin "4") (pinfunction "4_4") (pintype "passive"))
      (node (ref "JP17") (pin "1") (pinfunction "1_1") (pintype "passive"))
      (node (ref "U1") (pin "17") (pinfunction "PA7/SPI1_MOSI/ADC12_IN7/TIM3_CH2_17") (pintype "passive"))
      (node (ref "U8") (pin "6") (pinfunction "MOSI_6") (pintype "passive"))
      (node (ref "X1") (pin "9") (pinfunction "9_9") (pintype "passive"))
    )
    (net (code "49") (name "/NRF_CE") (class "Default")
      (node (ref "JP21") (pin "2") (pinfunction "2_2") (pintype "passive"))
      (node (ref "JP5") (pin "2") (pinfunction "2_2") (pintype "passive"))
      (node (ref "U1") (pin "12") (pinfunction "PA2/USART2_TX/ADC12_IN2/TIM2_CH3_12") (pintype "passive"))
      (node (ref "U8") (pin "3") (pinfunction "CE_3") (pintype "passive"))
      (node (ref "X1") (pin "14") (pinfunction "14_14") (pintype "passive"))
    )
    (net (code "50") (name "/NRF_CS") (class "Default")
      (node (ref "JP21") (pin "1") (pinfunction "1_1") (pintype "passive"))
      (node (ref "U1") (pin "11") (pinfunction "PA1/USART2_RTS/ADC12_IN1/TIM2_CH2_11") (pintype "passive"))
      (node (ref "U8") (pin "4") (pinfunction "CSN_4") (pintype "passive"))
      (node (ref "X1") (pin "15") (pinfunction "15_15") (pintype "passive"))
    )
    (net (code "51") (name "/NRF_IRQ") (class "Default")
      (node (ref "JP21") (pin "3") (pinfunction "3_3") (pintype "passive"))
      (node (ref "JP5") (pin "1") (pinfunction "1_1") (pintype "passive"))
      (node (ref "U1") (pin "13") (pinfunction "PA3/USART2_RX/ADC12_IN3/TIM2_CH4_13") (pintype "passive"))
      (node (ref "U8") (pin "8") (pinfunction "IRQ_8") (pintype "passive"))
      (node (ref "X1") (pin "13") (pinfunction "13_13") (pintype "passive"))
    )
    (net (code "52") (name "/OSC32_IN") (class "Default")
      (node (ref "C3") (pin "1") (pinfunction "1_1") (pintype "passive"))
      (node (ref "U1") (pin "3") (pinfunction "PC14-OSC32_IN_3") (pintype "passive"))
      (node (ref "Y2") (pin "1") (pinfunction "1_1") (pintype "passive"))
    )
    (net (code "53") (name "/OSC32_OUT") (class "Default")
      (node (ref "C2") (pin "1") (pinfunction "1_1") (pintype "passive"))
      (node (ref "U1") (pin "4") (pinfunction "PC15-OSC32_OUT_4") (pintype "passive"))
      (node (ref "Y2") (pin "2") (pinfunction "2_2") (pintype "passive"))
    )
    (net (code "54") (name "/OSC_IN") (class "Default")
      (node (ref "C5") (pin "1") (pinfunction "1_1") (pintype "passive"))
      (node (ref "U1") (pin "5") (pinfunction "PD0-OSC_IN_5") (pintype "passive"))
      (node (ref "Y1") (pin "1") (pinfunction "1_1") (pintype "passive"))
    )
    (net (code "55") (name "/OSC_OUT") (class "Default")
      (node (ref "C4") (pin "1") (pinfunction "1_1") (pintype "passive"))
      (node (ref "U1") (pin "6") (pinfunction "PD1-OSC_OUT_6") (pintype "passive"))
      (node (ref "Y1") (pin "2") (pinfunction "2_2") (pintype "passive"))
    )
    (net (code "56") (name "/OUT1") (class "Default")
      (node (ref "R27") (pin "1") (pintype "passive"))
      (node (ref "U10") (pin "15") (pinfunction "QA_15") (pintype "passive"))
    )
    (net (code "57") (name "/OUT2") (class "Default")
      (node (ref "R28") (pin "1") (pintype "passive"))
      (node (ref "U10") (pin "1") (pinfunction "QB_1") (pintype "passive"))
    )
    (net (code "58") (name "/OUT3") (class "Default")
      (node (ref "R29") (pin "1") (pintype "passive"))
      (node (ref "U10") (pin "2") (pinfunction "QC_2") (pintype "passive"))
    )
    (net (code "59") (name "/OUT4") (class "Default")
      (node (ref "R30") (pin "1") (pintype "passive"))
      (node (ref "U10") (pin "3") (pinfunction "QD_3") (pintype "passive"))
    )
    (net (code "60") (name "/PA8") (class "Default")
      (node (ref "JP7") (pin "1") (pinfunction "1_1") (pintype "passive"))
      (node (ref "LCD1") (pin "32") (pinfunction "XPT_PEN_32") (pintype "passive"))
      (node (ref "U1") (pin "29") (pinfunction "PA8/USART1_CK/TIM1_CH1/MCO_29") (pintype "passive"))
      (node (ref "X2") (pin "15") (pinfunction "15_15") (pintype "passive"))
    )
    (net (code "61") (name "/PA9") (class "Default")
      (node (ref "JP4") (pin "1") (pinfunction "1_1") (pintype "passive"))
      (node (ref "JP7") (pin "2") (pinfunction "2_2") (pintype "passive"))
      (node (ref "U1") (pin "30") (pinfunction "PA9/USART1_TX/TIM1_CH2_30") (pintype "passive"))
      (node (ref "X2") (pin "14") (pinfunction "14_14") (pintype "passive"))
    )
    (net (code "62") (name "/PB0") (class "Default")
      (node (ref "LCD1") (pin "28") (pinfunction "XPT_CS_28") (pintype "passive"))
      (node (ref "R4") (pin "2") (pinfunction "2_2") (pintype "passive"))
      (node (ref "U1") (pin "18") (pinfunction "PB0/ADC12_IN8/TIM3_CH3_18") (pintype "passive"))
      (node (ref "X1") (pin "8") (pinfunction "8_8") (pintype "passive"))
    )
    (net (code "63") (name "/PB13") (class "Default")
      (node (ref "LCD1") (pin "27") (pinfunction "XPT_SCK_27") (pintype "passive"))
      (node (ref "U1") (pin "26") (pinfunction "PB13/SPI2_SCK/USART3_CTS/TIM1_CH1N_26") (pintype "passive"))
      (node (ref "X1") (pin "2") (pinfunction "2_2") (pintype "passive"))
    )
    (net (code "64") (name "/PB14") (class "Default")
      (node (ref "LCD1") (pin "31") (pinfunction "XPT_MISO_31") (pintype "passive"))
      (node (ref "U1") (pin "27") (pinfunction "PB14/SPI2_MISO/USART3_RTS/TIM1_CH2N_27") (pintype "passive"))
      (node (ref "X1") (pin "1") (pinfunction "1_1") (pintype "passive"))
    )
    (net (code "65") (name "/PB15") (class "Default")
      (node (ref "LCD1") (pin "29") (pinfunction "XPT_MOSI_29") (pintype "passive"))
      (node (ref "U1") (pin "28") (pinfunction "PB15/SPI2_MOSI/TIM1_CH3N_28") (pintype "passive"))
      (node (ref "X2") (pin "16") (pinfunction "16_16") (pintype "passive"))
    )
    (net (code "66") (name "/R2OUT") (class "Default")
      (node (ref "JP6") (pin "1") (pinfunction "1_1") (pintype "passive"))
      (node (ref "U3") (pin "9") (pinfunction "R2OUT_9") (pintype "passive"))
    )
    (net (code "67") (name "/S1") (class "Default")
      (node (ref "Q1") (pin "12") (pinfunction "L_1_12") (pintype "passive"))
      (node (ref "V3") (pin "C") (pinfunction "C_C") (pintype "passive"))
    )
    (net (code "68") (name "/S2") (class "Default")
      (node (ref "Q1") (pin "9") (pinfunction "L_2_9") (pintype "passive"))
      (node (ref "V4") (pin "C") (pinfunction "C_C") (pintype "passive"))
    )
    (net (code "69") (name "/S3") (class "Default")
      (node (ref "Q1") (pin "8") (pinfunction "L_3_8") (pintype "passive"))
      (node (ref "V5") (pin "C") (pinfunction "C_C") (pintype "passive"))
    )
    (net (code "70") (name "/S4") (class "Default")
      (node (ref "Q1") (pin "6") (pinfunction "L_4_6") (pintype "passive"))
      (node (ref "V6") (pin "C") (pinfunction "C_C") (pintype "passive"))
    )
    (net (code "71") (name "/SP_CS") (class "Default")
      (node (ref "JP13") (pin "1") (pinfunction "1_1") (pintype "passive"))
      (node (ref "R8") (pin "1") (pinfunction "1_1") (pintype "passive"))
      (node (ref "U7") (pin "1") (pinfunction "~{CS}_1") (pintype "passive"))
    )
    (net (code "72") (name "/SP_MISO") (class "Default")
      (node (ref "JP13") (pin "3") (pinfunction "3_3") (pintype "passive"))
      (node (ref "U7") (pin "2") (pinfunction "DO_2") (pintype "passive"))
    )
    (net (code "73") (name "/SP_MOSI") (class "Default")
      (node (ref "JP13") (pin "4") (pinfunction "4_4") (pintype "passive"))
      (node (ref "U7") (pin "5") (pinfunction "DI_5") (pintype "passive"))
    )
    (net (code "74") (name "/SP_SCK") (class "Default")
      (node (ref "JP13") (pin "2") (pinfunction "2_2") (pintype "passive"))
      (node (ref "U7") (pin "6") (pinfunction "CLK_6") (pintype "passive"))
    )
    (net (code "75") (name "/T2IN") (class "Default")
      (node (ref "JP6") (pin "2") (pinfunction "2_2") (pintype "passive"))
      (node (ref "U3") (pin "10") (pinfunction "T2IN_10") (pintype "passive"))
    )
    (net (code "76") (name "/VBAT") (class "Default")
      (node (ref "C8") (pin "2") (pinfunction "2_2") (pintype "passive"))
      (node (ref "D1") (pin "2") (pinfunction "K_2") (pintype "passive"))
      (node (ref "D2") (pin "2") (pinfunction "K_2") (pintype "passive"))
      (node (ref "U1") (pin "1") (pinfunction "VBAT_1") (pintype "passive"))
    )
    (net (code "77") (name "3V3") (class "Default")
      (node (ref "BEEP1") (pin "1") (pinfunction "+_1") (pintype "passive"))
      (node (ref "C11") (pin "1") (pinfunction "1_1") (pintype "passive"))
      (node (ref "C12") (pin "1") (pinfunction "1_1") (pintype "passive"))
      (node (ref "C13") (pin "2") (pinfunction "2_2") (pintype "passive"))
      (node (ref "C16") (pin "1") (pinfunction "1_1") (pintype "passive"))
      (node (ref "C19") (pin "1") (pinfunction "1_1") (pintype "passive"))
      (node (ref "C20") (pin "2") (pinfunction "2_2") (pintype "passive"))
      (node (ref "C21") (pin "2") (pinfunction "2_2") (pintype "passive"))
      (node (ref "C22") (pin "1") (pinfunction "1_1") (pintype "passive"))
      (node (ref "C23") (pin "1") (pinfunction "1_1") (pintype "passive"))
      (node (ref "C24") (pin "1") (pinfunction "1_1") (pintype "passive"))
      (node (ref "C25") (pin "1") (pinfunction "1_1") (pintype "passive"))
      (node (ref "C26") (pin "2") (pinfunction "2_2") (pintype "passive"))
      (node (ref "C27") (pin "1") (pinfunction "1_1") (pintype "passive"))
      (node (ref "C28") (pin "1") (pinfunction "1_1") (pintype "passive"))
      (node (ref "D2") (pin "1") (pinfunction "A_1") (pintype "passive"))
      (node (ref "JP1") (pin "1") (pinfunction "1_1") (pintype "passive"))
      (node (ref "JP2") (pin "1") (pinfunction "1_1") (pintype "passive"))
      (node (ref "LCD1") (pin "2") (pinfunction "3V3_2") (pintype "passive"))
      (node (ref "N1") (pin "2") (pinfunction "VOUT_2") (pintype "passive"))
      (node (ref "N1") (pin "4") (pinfunction "VOUT_4") (pintype "passive"))
      (node (ref "R1") (pin "2") (pinfunction "2_2") (pintype "passive"))
      (node (ref "R11") (pin "2") (pinfunction "2_2") (pintype "passive"))
      (node (ref "R12") (pin "1") (pinfunction "1_1") (pintype "passive"))
      (node (ref "R13") (pin "1") (pinfunction "1_1") (pintype "passive"))
      (node (ref "R14") (pin "1") (pinfunction "1_1") (pintype "passive"))
      (node (ref "R15") (pin "1") (pinfunction "1_1") (pintype "passive"))
      (node (ref "R17") (pin "2") (pinfunction "2_2") (pintype "passive"))
      (node (ref "R18") (pin "2") (pinfunction "2_2") (pintype "passive"))
      (node (ref "R19") (pin "2") (pinfunction "2_2") (pintype "passive"))
      (node (ref "R20") (pin "2") (pinfunction "2_2") (pintype "passive"))
      (node (ref "R21") (pin "1") (pinfunction "1_1") (pintype "passive"))
      (node (ref "R22") (pin "1") (pinfunction "1_1") (pintype "passive"))
      (node (ref "R23") (pin "2") (pinfunction "2_2") (pintype "passive"))
      (node (ref "R24") (pin "2") (pinfunction "2_2") (pintype "passive"))
      (node (ref "R25") (pin "2") (pinfunction "2_2") (pintype "passive"))
      (node (ref "R26") (pin "2") (pinfunction "2_2") (pintype "passive"))
      (node (ref "R4") (pin "1") (pinfunction "1_1") (pintype "passive"))
      (node (ref "R5") (pin "2") (pinfunction "2_2") (pintype "passive"))
      (node (ref "R8") (pin "2") (pinfunction "2_2") (pintype "passive"))
      (node (ref "R9") (pin "1") (pinfunction "1_1") (pintype "passive"))
      (node (ref "U1") (pin "24") (pinfunction "VDD_1_24") (pintype "passive"))
      (node (ref "U1") (pin "36") (pinfunction "VDD_2_36") (pintype "passive"))
      (node (ref "U1") (pin "48") (pinfunction "VDD_3_48") (pintype "passive"))
      (node (ref "U1") (pin "9") (pinfunction "VDDA_9") (pintype "passive"))
      (node (ref "U10") (pin "16") (pinfunction "VCC_16") (pintype "passive"))
      (node (ref "U2") (pin "16") (pinfunction "VCC_16") (pintype "passive"))
      (node (ref "U2") (pin "4") (pinfunction "V3_4") (pintype "passive"))
      (node (ref "U3") (pin "16") (pinfunction "VCC_16") (pintype "passive"))
      (node (ref "U4") (pin "8") (pinfunction "VCC_8") (pintype "passive"))
      (node (ref "U5") (pin "3") (pinfunction "VCC_3") (pintype "passive"))
      (node (ref "U6") (pin "8") (pinfunction "VCC_8") (pintype "passive"))
      (node (ref "U7") (pin "3") (pinfunction "~{WP}_3") (pintype "passive"))
      (node (ref "U7") (pin "7") (pinfunction "~{HOLD}_7") (pintype "passive"))
      (node (ref "U7") (pin "8") (pinfunction "VCC_8") (pintype "passive"))
      (node (ref "U8") (pin "2") (pinfunction "VCC_2") (pintype "passive"))
      (node (ref "U9") (pin "16") (pinfunction "VCC_16") (pintype "passive"))
      (node (ref "X5") (pin "1") (pinfunction "1_1") (pintype "passive"))
      (node (ref "X5") (pin "2") (pinfunction "2_2") (pintype "passive"))
      (node (ref "X5") (pin "3") (pinfunction "3_3") (pintype "passive"))
      (node (ref "Z1") (pin "1") (pinfunction "1_1") (pintype "passive"))
      (node (ref "Z1") (pin "2") (pinfunction "2_2") (pintype "passive"))
    )
    (net (code "78") (name "5V") (class "Default")
      (node (ref "C10") (pin "1") (pinfunction "1_1") (pintype "passive"))
      (node (ref "C9") (pin "1") (pinfunction "1_1") (pintype "passive"))
      (node (ref "N1") (pin "3") (pinfunction "VIN_3") (pintype "passive"))
      (node (ref "S1") (pin "3") (pintype "passive"))
      (node (ref "X3") (pin "1") (pinfunction "1_1") (pintype "passive"))
      (node (ref "X3") (pin "2") (pinfunction "2_2") (pintype "passive"))
      (node (ref "X3") (pin "3") (pinfunction "3_3") (pintype "passive"))
    )
    (net (code "79") (name "GND") (class "Default")
      (node (ref "B1") (pin "2") (pinfunction "-_2") (pintype "passive"))
      (node (ref "C1") (pin "1") (pinfunction "1_1") (pintype "passive"))
      (node (ref "C10") (pin "2") (pinfunction "2_2") (pintype "passive"))
      (node (ref "C11") (pin "2") (pinfunction "2_2") (pintype "passive"))
      (node (ref "C12") (pin "2") (pinfunction "2_2") (pintype "passive"))
      (node (ref "C13") (pin "1") (pinfunction "1_1") (pintype "passive"))
      (node (ref "C16") (pin "2") (pinfunction "2_2") (pintype "passive"))
      (node (ref "C17") (pin "2") (pinfunction "2_2") (pintype "passive"))
      (node (ref "C18") (pin "2") (pinfunction "2_2") (pintype "passive"))
      (node (ref "C19") (pin "2") (pinfunction "2_2") (pintype "passive"))
      (node (ref "C2") (pin "2") (pinfunction "2_2") (pintype "passive"))
      (node (ref "C20") (pin "1") (pinfunction "1_1") (pintype "passive"))
      (node (ref "C21") (pin "1") (pinfunction "1_1") (pintype "passive"))
      (node (ref "C22") (pin "2") (pinfunction "2_2") (pintype "passive"))
      (node (ref "C23") (pin "2") (pinfunction "2_2") (pintype "passive"))
      (node (ref "C24") (pin "2") (pinfunction "2_2") (pintype "passive"))
      (node (ref "C25") (pin "2") (pinfunction "2_2") (pintype "passive"))
      (node (ref "C26") (pin "1") (pinfunction "1_1") (pintype "passive"))
      (node (ref "C27") (pin "2") (pinfunction "2_2") (pintype "passive"))
      (node (ref "C28") (pin "2") (pinfunction "2_2") (pintype "passive"))
      (node (ref "C3") (pin "2") (pinfunction "2_2") (pintype "passive"))
      (node (ref "C4") (pin "2") (pinfunction "2_2") (pintype "passive"))
      (node (ref "C5") (pin "2") (pinfunction "2_2") (pintype "passive"))
      (node (ref "C6") (pin "1") (pinfunction "1_1") (pintype "passive"))
      (node (ref "C7") (pin "1") (pinfunction "1_1") (pintype "passive"))
      (node (ref "C8") (pin "1") (pinfunction "1_1") (pintype "passive"))
      (node (ref "C9") (pin "2") (pinfunction "2_2") (pintype "passive"))
      (node (ref "DB1") (pin "5") (pinfunction "5_5") (pintype "passive"))
      (node (ref "H1") (pin "2") (pinfunction "K_2") (pintype "passive"))
      (node (ref "JP1") (pin "3") (pinfunction "3_3") (pintype "passive"))
      (node (ref "JP2") (pin "3") (pinfunction "3_3") (pintype "passive"))
      (node (ref "KEY1") (pin "1") (pinfunction "1_1") (pintype "passive"))
      (node (ref "KEY1") (pin "3") (pinfunction "3_3") (pintype "passive"))
      (node (ref "KEY2") (pin "1") (pinfunction "1_1") (pintype "passive"))
      (node (ref "KEY2") (pin "3") (pinfunction "3_3") (pintype "passive"))
      (node (ref "KEY3") (pin "1") (pinfunction "1_1") (pintype "passive"))
      (node (ref "KEY3") (pin "3") (pinfunction "3_3") (pintype "passive"))
      (node (ref "KEY4") (pin "1") (pinfunction "1_1") (pintype "passive"))
      (node (ref "KEY4") (pin "3") (pinfunction "3_3") (pintype "passive"))
      (node (ref "LCD1") (pin "1") (pinfunction "GND_1") (pintype "passive"))
      (node (ref "N1") (pin "1") (pinfunction "GND_1") (pintype "passive"))
      (node (ref "R16") (pin "2") (pinfunction "2_2") (pintype "passive"))
      (node (ref "R6") (pin "1") (pinfunction "1_1") (pintype "passive"))
      (node (ref "U1") (pin "23") (pinfunction "VSS_1_23") (pintype "passive"))
      (node (ref "U1") (pin "35") (pinfunction "VSS_2_35") (pintype "passive"))
      (node (ref "U1") (pin "47") (pinfunction "VSS_3_47") (pintype "passive"))
      (node (ref "U1") (pin "8") (pinfunction "VSSA_8") (pintype "passive"))
      (node (ref "U10") (pin "13") (pinfunction "~{EN}_13") (pintype "passive"))
      (node (ref "U10") (pin "8") (pinfunction "GND_8") (pintype "passive"))
      (node (ref "U2") (pin "1") (pinfunction "GND_1") (pintype "passive"))
      (node (ref "U3") (pin "15") (pinfunction "GND_15") (pintype "passive"))
      (node (ref "U4") (pin "5") (pinfunction "GND_5") (pintype "passive"))
      (node (ref "U5") (pin "2") (pinfunction "GND_2") (pintype "passive"))
      (node (ref "U5") (pin "8") (pinfunction "Rs_8") (pintype "passive"))
      (node (ref "U6") (pin "1") (pinfunction "A0_1") (pintype "passive"))
      (node (ref "U6") (pin "2") (pinfunction "A1_2") (pintype "passive"))
      (node (ref "U6") (pin "3") (pinfunction "A2_3") (pintype "passive"))
      (node (ref "U6") (pin "4") (pinfunction "GND_4") (pintype "passive"))
      (node (ref "U6") (pin "7") (pinfunction "WP_7") (pintype "passive"))
      (node (ref "U7") (pin "4") (pinfunction "GND_4") (pintype "passive"))
      (node (ref "U8") (pin "1") (pinfunction "GND_1") (pintype "passive"))
      (node (ref "U9") (pin "13") (pinfunction "~{EN}_13") (pintype "passive"))
      (node (ref "U9") (pin "8") (pinfunction "GND_8") (pintype "passive"))
      (node (ref "USB1") (pin "5") (pinfunction "GND_5") (pintype "passive"))
      (node (ref "USB2") (pin "5") (pinfunction "GND_5") (pintype "passive"))
      (node (ref "V1") (pin "E") (pinfunction "E_E") (pintype "passive"))
      (node (ref "V2") (pin "E") (pinfunction "E_E") (pintype "passive"))
      (node (ref "X4") (pin "1") (pinfunction "1_1") (pintype "passive"))
      (node (ref "X4") (pin "2") (pinfunction "2_2") (pintype "passive"))
      (node (ref "X4") (pin "3") (pinfunction "3_3") (pintype "passive"))
      (node (ref "X6") (pin "1") (pinfunction "1_1") (pintype "passive"))
      (node (ref "X6") (pin "2") (pinfunction "2_2") (pintype "passive"))
      (node (ref "X6") (pin "3") (pinfunction "3_3") (pintype "passive"))
      (node (ref "Z1") (pin "10") (pinfunction "10_10") (pintype "passive"))
      (node (ref "Z1") (pin "12") (pinfunction "12_12") (pintype "passive"))
      (node (ref "Z1") (pin "14") (pinfunction "14_14") (pintype "passive"))
      (node (ref "Z1") (pin "16") (pinfunction "16_16") (pintype "passive"))
      (node (ref "Z1") (pin "18") (pinfunction "18_18") (pintype "passive"))
      (node (ref "Z1") (pin "20") (pinfunction "20_20") (pintype "passive"))
      (node (ref "Z1") (pin "4") (pinfunction "4_4") (pintype "passive"))
      (node (ref "Z1") (pin "6") (pinfunction "6_6") (pintype "passive"))
      (node (ref "Z1") (pin "8") (pinfunction "8_8") (pintype "passive"))
    )
    (net (code "80") (name "Net-(B1-+)") (class "Default")
      (node (ref "B1") (pin "1") (pinfunction "+_1") (pintype "passive"))
      (node (ref "D1") (pin "1") (pinfunction "A_1") (pintype "passive"))
    )
    (net (code "81") (name "Net-(BEEP1--)") (class "Default")
      (node (ref "BEEP1") (pin "2") (pinfunction "-_2") (pintype "passive"))
      (node (ref "V2") (pin "C") (pinfunction "C_C") (pintype "passive"))
    )
    (net (code "82") (name "Net-(H1-A)") (class "Default")
      (node (ref "H1") (pin "1") (pinfunction "A_1") (pintype "passive"))
      (node (ref "R9") (pin "2") (pinfunction "2_2") (pintype "passive"))
    )
    (net (code "83") (name "Net-(H2-A)") (class "Default")
      (node (ref "H2") (pin "1") (pinfunction "A_1") (pintype "passive"))
      (node (ref "R12") (pin "2") (pinfunction "2_2") (pintype "passive"))
    )
    (net (code "84") (name "Net-(H2-K)") (class "Default")
      (node (ref "H2") (pin "2") (pinfunction "K_2") (pintype "passive"))
      (node (ref "JP16") (pin "1") (pinfunction "1_1") (pintype "passive"))
    )
    (net (code "85") (name "Net-(H3-A)") (class "Default")
      (node (ref "H3") (pin "1") (pinfunction "A_1") (pintype "passive"))
      (node (ref "R13") (pin "2") (pinfunction "2_2") (pintype "passive"))
    )
    (net (code "86") (name "Net-(H3-K)") (class "Default")
      (node (ref "H3") (pin "2") (pinfunction "K_2") (pintype "passive"))
      (node (ref "JP16") (pin "2") (pinfunction "2_2") (pintype "passive"))
    )
    (net (code "87") (name "Net-(H4-A)") (class "Default")
      (node (ref "H4") (pin "1") (pinfunction "A_1") (pintype "passive"))
      (node (ref "R14") (pin "2") (pinfunction "2_2") (pintype "passive"))
    )
    (net (code "88") (name "Net-(H4-K)") (class "Default")
      (node (ref "H4") (pin "2") (pinfunction "K_2") (pintype "passive"))
      (node (ref "JP16") (pin "3") (pinfunction "3_3") (pintype "passive"))
    )
    (net (code "89") (name "Net-(H5-A)") (class "Default")
      (node (ref "H5") (pin "1") (pinfunction "A_1") (pintype "passive"))
      (node (ref "R15") (pin "2") (pinfunction "2_2") (pintype "passive"))
    )
    (net (code "90") (name "Net-(H5-K)") (class "Default")
      (node (ref "H5") (pin "2") (pinfunction "K_2") (pintype "passive"))
      (node (ref "JP16") (pin "4") (pinfunction "4_4") (pintype "passive"))
    )
    (net (code "91") (name "Net-(JP1-Pad2)") (class "Default")
      (node (ref "JP1") (pin "2") (pinfunction "2_2") (pintype "passive"))
      (node (ref "R2") (pin "2") (pinfunction "2_2") (pintype "passive"))
    )
    (net (code "92") (name "Net-(JP2-Pad2)") (class "Default")
      (node (ref "JP2") (pin "2") (pinfunction "2_2") (pintype "passive"))
      (node (ref "R3") (pin "2") (pinfunction "2_2") (pintype "passive"))
    )
    (net (code "93") (name "Net-(JP15-Pad1)") (class "Default")
      (node (ref "JP15") (pin "1") (pinfunction "1_1") (pintype "passive"))
      (node (ref "R7") (pin "1") (pinfunction "1_1") (pintype "passive"))
    )
    (net (code "94") (name "Net-(R6-Pad2)") (class "Default")
      (node (ref "R6") (pin "2") (pinfunction "2_2") (pintype "passive"))
      (node (ref "R7") (pin "2") (pinfunction "2_2") (pintype "passive"))
      (node (ref "V2") (pin "B") (pinfunction "B_B") (pintype "passive"))
    )
    (net (code "95") (name "Net-(R10-Pad2)") (class "Default")
      (node (ref "R10") (pin "2") (pinfunction "2_2") (pintype "passive"))
      (node (ref "V1") (pin "B") (pinfunction "B_B") (pintype "passive"))
    )
    (net (code "96") (name "Net-(R23-Pad1)") (class "Default")
      (node (ref "R23") (pin "1") (pinfunction "1_1") (pintype "passive"))
      (node (ref "V3") (pin "E") (pinfunction "E_E") (pintype "passive"))
    )
    (net (code "97") (name "Net-(R24-Pad1)") (class "Default")
      (node (ref "R24") (pin "1") (pinfunction "1_1") (pintype "passive"))
      (node (ref "V4") (pin "E") (pinfunction "E_E") (pintype "passive"))
    )
    (net (code "98") (name "Net-(R25-Pad1)") (class "Default")
      (node (ref "R25") (pin "1") (pinfunction "1_1") (pintype "passive"))
      (node (ref "V5") (pin "E") (pinfunction "E_E") (pintype "passive"))
    )
    (net (code "99") (name "Net-(R26-Pad1)") (class "Default")
      (node (ref "R26") (pin "1") (pinfunction "1_1") (pintype "passive"))
      (node (ref "V6") (pin "E") (pinfunction "E_E") (pintype "passive"))
    )
    (net (code "100") (name "Net-(R27-Pad2)") (class "Default")
      (node (ref "R27") (pin "2") (pintype "passive"))
      (node (ref "V3") (pin "B") (pinfunction "B_B") (pintype "passive"))
    )
    (net (code "101") (name "Net-(R28-Pad2)") (class "Default")
      (node (ref "R28") (pin "2") (pintype "passive"))
      (node (ref "V4") (pin "B") (pinfunction "B_B") (pintype "passive"))
    )
    (net (code "102") (name "Net-(R29-Pad2)") (class "Default")
      (node (ref "R29") (pin "2") (pintype "passive"))
      (node (ref "V5") (pin "B") (pinfunction "B_B") (pintype "passive"))
    )
    (net (code "103") (name "Net-(R30-Pad2)") (class "Default")
      (node (ref "R30") (pin "2") (pintype "passive"))
      (node (ref "V6") (pin "B") (pinfunction "B_B") (pintype "passive"))
    )
    (net (code "104") (name "Net-(U2-UD+)") (class "Default")
      (node (ref "U2") (pin "5") (pinfunction "UD+_5") (pintype "passive"))
      (node (ref "USB1") (pin "3") (pinfunction "D+_3") (pintype "passive"))
    )
    (net (code "105") (name "Net-(U2-UD-)") (class "Default")
      (node (ref "U2") (pin "6") (pinfunction "UD-_6") (pintype "passive"))
      (node (ref "USB1") (pin "2") (pinfunction "D-_2") (pintype "passive"))
    )
    (net (code "106") (name "Net-(U2-~{RTS})") (class "Default")
      (node (ref "R10") (pin "1") (pinfunction "1_1") (pintype "passive"))
      (node (ref "U2") (pin "14") (pinfunction "~{RTS}_14") (pintype "passive"))
    )
    (net (code "107") (name "Net-(U3-C1+)") (class "Default")
      (node (ref "C14") (pin "2") (pinfunction "2_2") (pintype "passive"))
      (node (ref "U3") (pin "1") (pinfunction "C1+_1") (pintype "passive"))
    )
    (net (code "108") (name "Net-(U3-C1-)") (class "Default")
      (node (ref "C14") (pin "1") (pinfunction "1_1") (pintype "passive"))
      (node (ref "U3") (pin "3") (pinfunction "C1-_3") (pintype "passive"))
    )
    (net (code "109") (name "Net-(U3-C2+)") (class "Default")
      (node (ref "C15") (pin "2") (pinfunction "2_2") (pintype "passive"))
      (node (ref "U3") (pin "4") (pinfunction "C2+_4") (pintype "passive"))
    )
    (net (code "110") (name "Net-(U3-C2-)") (class "Default")
      (node (ref "C15") (pin "1") (pinfunction "1_1") (pintype "passive"))
      (node (ref "U3") (pin "5") (pinfunction "C2-_5") (pintype "passive"))
    )
    (net (code "111") (name "Net-(U3-R2IN)") (class "Default")
      (node (ref "DB1") (pin "3") (pinfunction "3_3") (pintype "passive"))
      (node (ref "U3") (pin "8") (pinfunction "R2IN_8") (pintype "passive"))
    )
    (net (code "112") (name "Net-(U3-T2OUT)") (class "Default")
      (node (ref "DB1") (pin "2") (pinfunction "2_2") (pintype "passive"))
      (node (ref "U3") (pin "7") (pinfunction "T2OUT_7") (pintype "passive"))
    )
    (net (code "113") (name "Net-(U3-V+)") (class "Default")
      (node (ref "C18") (pin "1") (pinfunction "1_1") (pintype "passive"))
      (node (ref "U3") (pin "2") (pinfunction "V+_2") (pintype "passive"))
    )
    (net (code "114") (name "Net-(U3-V-)") (class "Default")
      (node (ref "C17") (pin "1") (pinfunction "1_1") (pintype "passive"))
      (node (ref "U3") (pin "6") (pinfunction "V-_6") (pintype "passive"))
    )
    (net (code "115") (name "Net-(U4-A)") (class "Default")
      (node (ref "R17") (pin "1") (pinfunction "1_1") (pintype "passive"))
      (node (ref "U4") (pin "6") (pinfunction "A_6") (pintype "passive"))
      (node (ref "X7") (pin "2") (pinfunction "2_2") (pintype "passive"))
    )
    (net (code "116") (name "Net-(U4-B)") (class "Default")
      (node (ref "R16") (pin "1") (pinfunction "1_1") (pintype "passive"))
      (node (ref "U4") (pin "7") (pinfunction "B_7") (pintype "passive"))
      (node (ref "X7") (pin "1") (pinfunction "1_1") (pintype "passive"))
    )
    (net (code "117") (name "Net-(U4-DE)") (class "Default")
      (node (ref "JP8") (pin "1") (pinfunction "1_1") (pintype "passive"))
      (node (ref "U4") (pin "2") (pinfunction "~{RE}_2") (pintype "passive"))
      (node (ref "U4") (pin "3") (pinfunction "DE_3") (pintype "passive"))
    )
    (net (code "118") (name "Net-(U4-DI)") (class "Default")
      (node (ref "JP8") (pin "2") (pinfunction "2_2") (pintype "passive"))
      (node (ref "U4") (pin "4") (pinfunction "DI_4") (pintype "passive"))
    )
    (net (code "119") (name "Net-(U4-RO)") (class "Default")
      (node (ref "JP8") (pin "3") (pinfunction "3_3") (pintype "passive"))
      (node (ref "U4") (pin "1") (pinfunction "RO_1") (pintype "passive"))
    )
    (net (code "120") (name "Net-(U5-CANH)") (class "Default")
      (node (ref "U5") (pin "7") (pinfunction "CANH_7") (pintype "passive"))
      (node (ref "X8") (pin "1") (pinfunction "1_1") (pintype "passive"))
    )
    (net (code "121") (name "Net-(U5-CANL)") (class "Default")
      (node (ref "U5") (pin "6") (pinfunction "CANL_6") (pintype "passive"))
      (node (ref "X8") (pin "2") (pinfunction "2_2") (pintype "passive"))
    )
    (net (code "122") (name "Net-(U5-RXD)") (class "Default")
      (node (ref "JP10") (pin "2") (pinfunction "2_2") (pintype "passive"))
      (node (ref "U5") (pin "4") (pinfunction "RXD_4") (pintype "passive"))
    )
    (net (code "123") (name "Net-(U5-TXD)") (class "Default")
      (node (ref "JP10") (pin "1") (pinfunction "1_1") (pintype "passive"))
      (node (ref "U5") (pin "1") (pinfunction "TXD_1") (pintype "passive"))
    )
    (net (code "124") (name "Net-(U9-RESET)") (class "Default")
      (node (ref "R21") (pin "2") (pinfunction "2_2") (pintype "passive"))
      (node (ref "U9") (pin "10") (pinfunction "RESET_10") (pintype "passive"))
    )
    (net (code "125") (name "Net-(U10-RESET)") (class "Default")
      (node (ref "R22") (pin "2") (pinfunction "2_2") (pintype "passive"))
      (node (ref "U10") (pin "10") (pinfunction "RESET_10") (pintype "passive"))
    )
    (net (code "126") (name "VUSB") (class "Default")
      (node (ref "S1") (pin "2") (pintype "passive"))
      (node (ref "USB1") (pin "1") (pinfunction "VCC_1") (pintype "passive"))
      (node (ref "USB2") (pin "1") (pinfunction "VCC_1") (pintype "passive"))
    )
    (net (code "127") (name "unconnected-(DB1-Pad1)") (class "Default")
      (node (ref "DB1") (pin "1") (pinfunction "1_1") (pintype "passive"))
    )
    (net (code "128") (name "unconnected-(DB1-Pad4)") (class "Default")
      (node (ref "DB1") (pin "4") (pinfunction "4_4") (pintype "passive"))
    )
    (net (code "129") (name "unconnected-(DB1-Pad6)") (class "Default")
      (node (ref "DB1") (pin "6") (pinfunction "6_6") (pintype "passive"))
    )
    (net (code "130") (name "unconnected-(DB1-Pad7)") (class "Default")
      (node (ref "DB1") (pin "7") (pinfunction "7_7") (pintype "passive"))
    )
    (net (code "131") (name "unconnected-(DB1-Pad8)") (class "Default")
      (node (ref "DB1") (pin "8") (pinfunction "8_8") (pintype "passive"))
    )
    (net (code "132") (name "unconnected-(DB1-Pad9)") (class "Default")
      (node (ref "DB1") (pin "9") (pinfunction "9_9") (pintype "passive"))
    )
    (net (code "133") (name "unconnected-(LCD1-DB0-Pad10)") (class "Default")
      (node (ref "LCD1") (pin "10") (pinfunction "DB0_10") (pintype "passive"))
    )
    (net (code "134") (name "unconnected-(LCD1-DB1-Pad11)") (class "Default")
      (node (ref "LCD1") (pin "11") (pinfunction "DB1_11") (pintype "passive"))
    )
    (net (code "135") (name "unconnected-(LCD1-DB2-Pad12)") (class "Default")
      (node (ref "LCD1") (pin "12") (pinfunction "DB2_12") (pintype "passive"))
    )
    (net (code "136") (name "unconnected-(LCD1-DB3-Pad13)") (class "Default")
      (node (ref "LCD1") (pin "13") (pinfunction "DB3_13") (pintype "passive"))
    )
    (net (code "137") (name "unconnected-(LCD1-DB4-Pad14)") (class "Default")
      (node (ref "LCD1") (pin "14") (pinfunction "DB4_14") (pintype "passive"))
    )
    (net (code "138") (name "unconnected-(LCD1-DB5-Pad15)") (class "Default")
      (node (ref "LCD1") (pin "15") (pinfunction "DB5_15") (pintype "passive"))
    )
    (net (code "139") (name "unconnected-(LCD1-DB6-Pad16)") (class "Default")
      (node (ref "LCD1") (pin "16") (pinfunction "DB6_16") (pintype "passive"))
    )
    (net (code "140") (name "unconnected-(LCD1-DB7-Pad17)") (class "Default")
      (node (ref "LCD1") (pin "17") (pinfunction "DB7_17") (pintype "passive"))
    )
    (net (code "141") (name "unconnected-(LCD1-LCD_MISO-Pad8)") (class "Default")
      (node (ref "LCD1") (pin "8") (pinfunction "LCD_MISO_8") (pintype "passive"))
    )
    (net (code "142") (name "unconnected-(LCD1-LCD_MOSI-Pad7)") (class "Default")
      (node (ref "LCD1") (pin "7") (pinfunction "LCD_MOSI_7") (pintype "passive"))
    )
    (net (code "143") (name "unconnected-(LCD1-XPT_BUSY-Pad30)") (class "Default")
      (node (ref "LCD1") (pin "30") (pinfunction "XPT_BUSY_30") (pintype "passive"))
    )
    (net (code "144") (name "unconnected-(S1-Pad1)") (class "Default")
      (node (ref "S1") (pin "1") (pintype "passive"))
    )
    (net (code "145") (name "unconnected-(S1-Pad4)") (class "Default")
      (node (ref "S1") (pin "4") (pintype "passive"))
    )
    (net (code "146") (name "unconnected-(S1-Pad5)") (class "Default")
      (node (ref "S1") (pin "5") (pintype "passive"))
    )
    (net (code "147") (name "unconnected-(S1-Pad6)") (class "Default")
      (node (ref "S1") (pin "6") (pintype "passive"))
    )
    (net (code "148") (name "unconnected-(U2-R232-Pad15)") (class "Default")
      (node (ref "U2") (pin "15") (pinfunction "R232_15") (pintype "passive"))
    )
    (net (code "149") (name "unconnected-(U2-~{CTS}-Pad9)") (class "Default")
      (node (ref "U2") (pin "9") (pinfunction "~{CTS}_9") (pintype "passive"))
    )
    (net (code "150") (name "unconnected-(U2-~{DCD}-Pad12)") (class "Default")
      (node (ref "U2") (pin "12") (pinfunction "~{DCD}_12") (pintype "passive"))
    )
    (net (code "151") (name "unconnected-(U2-~{DSR}-Pad10)") (class "Default")
      (node (ref "U2") (pin "10") (pinfunction "~{DSR}_10") (pintype "passive"))
    )
    (net (code "152") (name "unconnected-(U2-~{RI}-Pad11)") (class "Default")
      (node (ref "U2") (pin "11") (pinfunction "~{RI}_11") (pintype "passive"))
    )
    (net (code "153") (name "unconnected-(U3-R1IN-Pad13)") (class "Default")
      (node (ref "U3") (pin "13") (pinfunction "R1IN_13") (pintype "passive"))
    )
    (net (code "154") (name "unconnected-(U3-R1OUT-Pad12)") (class "Default")
      (node (ref "U3") (pin "12") (pinfunction "R1OUT_12") (pintype "passive"))
    )
    (net (code "155") (name "unconnected-(U3-T1IN-Pad11)") (class "Default")
      (node (ref "U3") (pin "11") (pinfunction "T1IN_11") (pintype "passive"))
    )
    (net (code "156") (name "unconnected-(U3-T1OUT-Pad14)") (class "Default")
      (node (ref "U3") (pin "14") (pinfunction "T1OUT_14") (pintype "passive"))
    )
    (net (code "157") (name "unconnected-(U5-Vref-Pad5)") (class "Default")
      (node (ref "U5") (pin "5") (pinfunction "Vref_5") (pintype "passive"))
    )
    (net (code "158") (name "unconnected-(U10-QE-Pad4)") (class "Default")
      (node (ref "U10") (pin "4") (pinfunction "QE_4") (pintype "passive"))
    )
    (net (code "159") (name "unconnected-(U10-QF-Pad5)") (class "Default")
      (node (ref "U10") (pin "5") (pinfunction "QF_5") (pintype "passive"))
    )
    (net (code "160") (name "unconnected-(U10-QG-Pad6)") (class "Default")
      (node (ref "U10") (pin "6") (pinfunction "QG_6") (pintype "passive"))
    )
    (net (code "161") (name "unconnected-(U10-QH-Pad7)") (class "Default")
      (node (ref "U10") (pin "7") (pinfunction "QH_7") (pintype "passive"))
    )
    (net (code "162") (name "unconnected-(U10-SQH-Pad9)") (class "Default")
      (node (ref "U10") (pin "9") (pinfunction "SQH_9") (pintype "passive"))
    )
    (net (code "163") (name "unconnected-(USB1-NC-Pad4)") (class "Default")
      (node (ref "USB1") (pin "4") (pinfunction "NC_4") (pintype "passive"))
    )
    (net (code "164") (name "unconnected-(USB2-NC-Pad4)") (class "Default")
      (node (ref "USB2") (pin "4") (pinfunction "NC_4") (pintype "passive"))
    )
    (net (code "165") (name "unconnected-(Z1-Pad11)") (class "Default")
      (node (ref "Z1") (pin "11") (pinfunction "11_11") (pintype "passive+no_connect"))
    )
    (net (code "166") (name "unconnected-(Z1-Pad17)") (class "Default")
      (node (ref "Z1") (pin "17") (pinfunction "17_17") (pintype "passive+no_connect"))
    )
    (net (code "167") (name "unconnected-(Z1-Pad19)") (class "Default")
      (node (ref "Z1") (pin "19") (pinfunction "19_19") (pintype "passive+no_connect"))
    )
  )
)
